# DAC_Board.net
KiCad netlist of a schematic drawn in Altium Designer
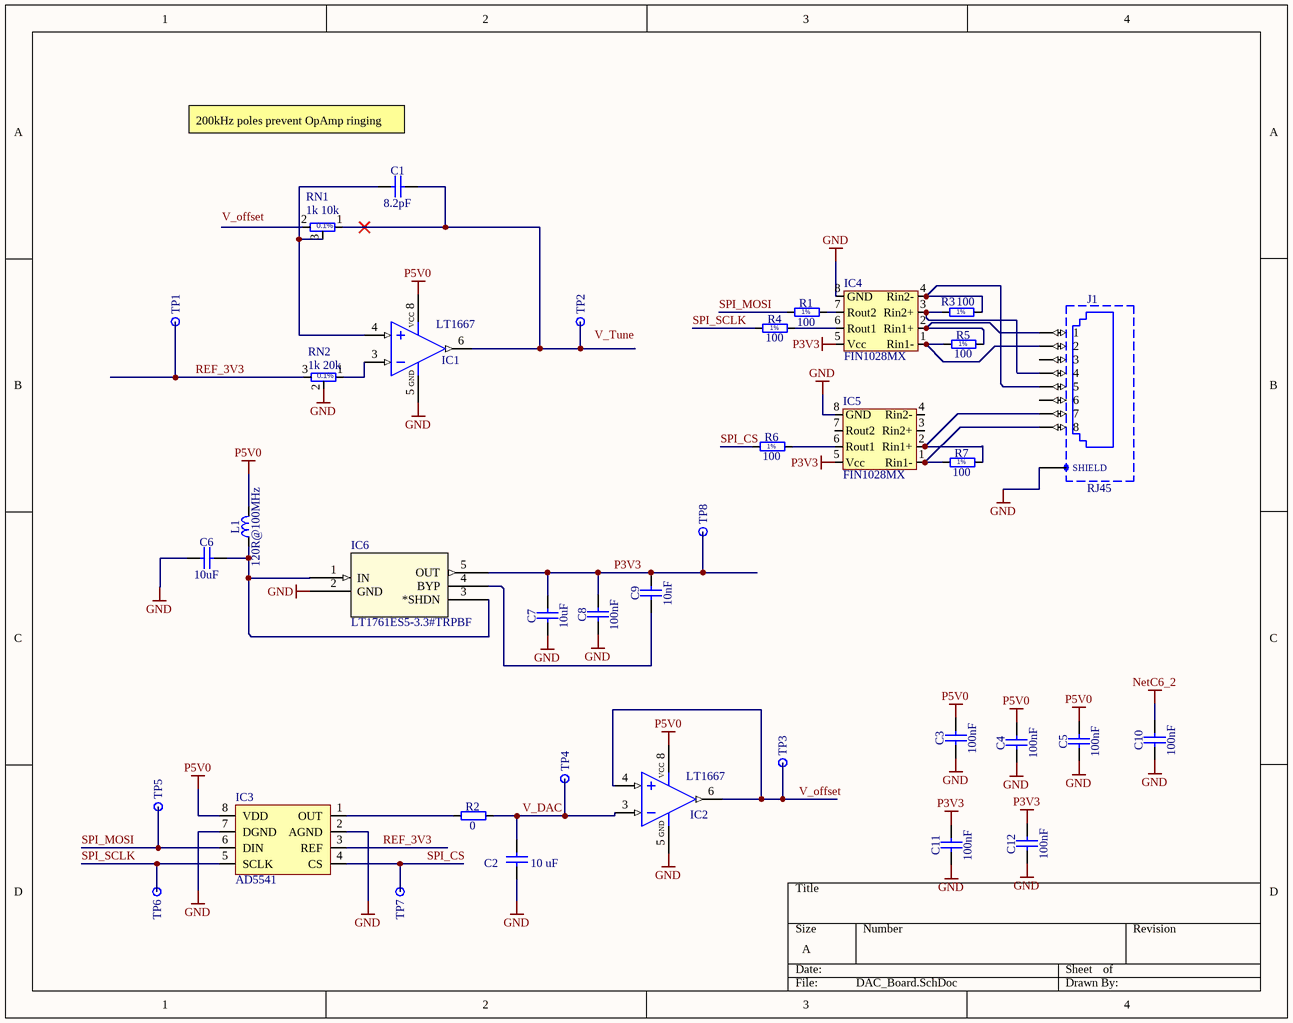
[diagram p0: DAC_Board.SchDoc]

(export (version "E")
  (design (tool "Eeschema 10.0.6"))
  (components
    (comp (ref "C1")
      (value "8.2pF")
      (footprint "CAPC1608X87N")
      (description "Non-polarised capacitor")
      (fields
        (field (name "PART NUMBER") "CC0603_8.2PF_50V_0.5PF_NP0")
        (field (name "VOLTAGE") "50V")
        (field (name "AUTHOR") "CERN DEM JLC")
      )
      (libsource (lib "Capacitors") (part "Capacitor - non polarized"))
    )
    (comp (ref "C2")
      (value "10 uF")
      (footprint "Capacitors SMD:CAPC5750X279N")
      (libsource (lib "Addons") (part "CAPF2220_10uF_35V_20%"))
    )
    (comp (ref "C3")
      (value "100nF")
      (footprint "CAPC1608X87N")
      (description "Non-polarised capacitor")
      (fields
        (field (name "PART NUMBER") "CC0603_100NF_50V_10%_X7R")
        (field (name "VOLTAGE") "50V")
        (field (name "AUTHOR") "CERN DEM JLC")
      )
      (libsource (lib "Capacitors") (part "Capacitor - non polarized"))
    )
    (comp (ref "C4")
      (value "100nF")
      (footprint "CAPC1608X87N")
      (description "Non-polarised capacitor")
      (fields
        (field (name "PART NUMBER") "CC0603_100NF_50V_10%_X7R")
        (field (name "VOLTAGE") "50V")
        (field (name "AUTHOR") "CERN DEM JLC")
      )
      (libsource (lib "Capacitors") (part "Capacitor - non polarized"))
    )
    (comp (ref "C5")
      (value "100nF")
      (footprint "CAPC1608X87N")
      (description "Non-polarised capacitor")
      (fields
        (field (name "PART NUMBER") "CC0603_100NF_50V_10%_X7R")
        (field (name "VOLTAGE") "50V")
        (field (name "AUTHOR") "CERN DEM JLC")
      )
      (libsource (lib "Capacitors") (part "Capacitor - non polarized"))
    )
    (comp (ref "C6")
      (value "10uF")
      (footprint "CAPC3216X180N")
      (description "Non-polarised capacitor")
      (fields
        (field (name "PART NUMBER") "CC1206_10UF_25V_10%_X7R")
        (field (name "VOLTAGE") "25V")
        (field (name "AUTHOR") "CERN DEM JLC")
      )
      (libsource (lib "Capacitors") (part "Capacitor - non polarized"))
    )
    (comp (ref "C7")
      (value "10uF")
      (footprint "CAPC3216X180N")
      (description "Non-polarised capacitor")
      (fields
        (field (name "PART NUMBER") "CC1206_10UF_25V_10%_X7R")
        (field (name "VOLTAGE") "25V")
        (field (name "AUTHOR") "CERN DEM JLC")
      )
      (libsource (lib "Capacitors") (part "Capacitor - non polarized"))
    )
    (comp (ref "C8")
      (value "100nF")
      (footprint "CAPC1608X87N")
      (description "Non-polarised capacitor")
      (fields
        (field (name "PART NUMBER") "CC0603_100NF_50V_10%_X7R")
        (field (name "VOLTAGE") "50V")
        (field (name "AUTHOR") "CERN DEM JLC")
      )
      (libsource (lib "Capacitors") (part "Capacitor - non polarized"))
    )
    (comp (ref "C9")
      (value "10nF")
      (footprint "CAPC1608X87N")
      (description "Non-polarised capacitor")
      (fields
        (field (name "PART NUMBER") "CC0603_10NF_50V_10%_X7R")
        (field (name "VOLTAGE") "50V")
        (field (name "AUTHOR") "CERN DEM JLC")
      )
      (libsource (lib "Capacitors") (part "Capacitor - non polarized"))
    )
    (comp (ref "C10")
      (value "100nF")
      (footprint "CAPC1608X87N")
      (description "Non-polarised capacitor")
      (fields
        (field (name "PART NUMBER") "CC0603_100NF_50V_10%_X7R")
        (field (name "VOLTAGE") "50V")
        (field (name "AUTHOR") "CERN DEM JLC")
      )
      (libsource (lib "Capacitors") (part "Capacitor - non polarized"))
    )
    (comp (ref "C11")
      (value "100nF")
      (footprint "CAPC1608X87N")
      (description "Non-polarised capacitor")
      (fields
        (field (name "PART NUMBER") "CC0603_100NF_50V_10%_X7R")
        (field (name "VOLTAGE") "50V")
        (field (name "AUTHOR") "CERN DEM JLC")
      )
      (libsource (lib "Capacitors") (part "Capacitor - non polarized"))
    )
    (comp (ref "C12")
      (value "100nF")
      (footprint "CAPC1608X87N")
      (description "Non-polarised capacitor")
      (fields
        (field (name "PART NUMBER") "CC0603_100NF_50V_10%_X7R")
        (field (name "VOLTAGE") "50V")
        (field (name "AUTHOR") "CERN DEM JLC")
      )
      (libsource (lib "Capacitors") (part "Capacitor - non polarized"))
    )
    (comp (ref "IC1")
      (value "LT1667")
      (footprint "SOIC127P600X175-8N")
      (description "0-5 V Rail to Rail op amp")
      (libsource (lib "LIBRARY_SCH") (part "LT1667"))
    )
    (comp (ref "IC2")
      (value "LT1667")
      (footprint "SOIC127P600X175-8N")
      (description "0-5 V Rail to Rail op amp")
      (libsource (lib "LIBRARY_SCH") (part "LT1667"))
    )
    (comp (ref "IC3")
      (value "AD5541")
      (footprint "AD5541")
      (description "16 bit serial DAC")
      (libsource (lib "LIBRARY_SCH") (part "AD5541"))
    )
    (comp (ref "IC4")
      (value "FIN1028MX")
      (footprint "FIN1028MX")
      (description "LVDS to TTL")
      (libsource (lib "LIBRARY_SCH") (part "FIN1028MX"))
    )
    (comp (ref "IC5")
      (value "FIN1028MX")
      (footprint "FIN1028MX")
      (description "LVDS to TTL")
      (libsource (lib "LIBRARY_SCH") (part "FIN1028MX"))
    )
    (comp (ref "IC6")
      (value "LT1761ES5-3.3#TRPBF")
      (footprint "LDO")
      (description "3.3 V LDO")
      (libsource (lib "LIBRARY_SCH") (part "LT1761ES5-3.3#TRPBF"))
    )
    (comp (ref "J1")
      (value "RJ45")
      (footprint "TYCO_6368150-1")
      (description "Connector RJ45 + Shield")
      (fields
        (field (name "PART NUMBER") "TYCO_6368150-1")
        (field (name "MANUFACTURER") "TYCO ELECTRONICS")
        (field (name "AUTHOR") "CERN DEM MR")
      )
      (libsource (lib "Connectors") (part "Connector RJ45 + Shield"))
    )
    (comp (ref "L1")
      (value "120R@100MHz")
      (footprint "INDC1608X95N")
      (description "Inductor")
      (fields
        (field (name "PART NUMBER") "IND0603_MURATA_BLM18PG121SN1D")
        (field (name "POWER") "2A")
        (field (name "AUTHOR") "CERN DEM BC")
      )
      (libsource (lib "Inductors & Transformers") (part "Inductor"))
    )
    (comp (ref "R1")
      (value "100")
      (footprint "RESC1608X55N")
      (description "Resistor - 1%")
      (fields
        (field (name "PART NUMBER") "R0603_100R_1%_0.1W_100PPM")
        (field (name "POWER") "0.1W")
        (field (name "AUTHOR") "CERN DEM JLC")
      )
      (libsource (lib "Resistors") (part "Resistor - 1%"))
    )
    (comp (ref "R2")
      (value "0")
      (footprint "RESC1608X55N")
      (description "Resistor")
      (fields
        (field (name "PART NUMBER") "R0603_0R_JUMPER")
        (field (name "MANUFACTURER") "GENERIC")
        (field (name "AUTHOR") "CERN DEM JLC")
      )
      (libsource (lib "Resistors") (part "Resistor"))
    )
    (comp (ref "R3")
      (value "100")
      (footprint "RESC1608X55N")
      (description "Resistor - 1%")
      (fields
        (field (name "PART NUMBER") "R0603_100R_1%_0.1W_100PPM")
        (field (name "POWER") "0.1W")
        (field (name "AUTHOR") "CERN DEM JLC")
      )
      (libsource (lib "Resistors") (part "Resistor - 1%"))
    )
    (comp (ref "R4")
      (value "100")
      (footprint "RESC1608X55N")
      (description "Resistor - 1%")
      (fields
        (field (name "PART NUMBER") "R0603_100R_1%_0.1W_100PPM")
        (field (name "POWER") "0.1W")
        (field (name "AUTHOR") "CERN DEM JLC")
      )
      (libsource (lib "Resistors") (part "Resistor - 1%"))
    )
    (comp (ref "R5")
      (value "100")
      (footprint "RESC1608X55N")
      (description "Resistor - 1%")
      (fields
        (field (name "PART NUMBER") "R0603_100R_1%_0.1W_100PPM")
        (field (name "POWER") "0.1W")
        (field (name "AUTHOR") "CERN DEM JLC")
      )
      (libsource (lib "Resistors") (part "Resistor - 1%"))
    )
    (comp (ref "R6")
      (value "100")
      (footprint "RESC1608X55N")
      (description "Resistor - 1%")
      (fields
        (field (name "PART NUMBER") "R0603_100R_1%_0.1W_100PPM")
        (field (name "POWER") "0.1W")
        (field (name "AUTHOR") "CERN DEM JLC")
      )
      (libsource (lib "Resistors") (part "Resistor - 1%"))
    )
    (comp (ref "R7")
      (value "100")
      (footprint "RESC1608X55N")
      (description "Resistor - 1%")
      (fields
        (field (name "PART NUMBER") "R0603_100R_1%_0.1W_100PPM")
        (field (name "POWER") "0.1W")
        (field (name "AUTHOR") "CERN DEM JLC")
      )
      (libsource (lib "Resistors") (part "Resistor - 1%"))
    )
    (comp (ref "RN1")
      (value "~")
      (footprint "SOT95P230X112-3N")
      (description "Resistor Network Divider - 0.1%")
      (libsource (lib "LIBRARY_SCH") (part "RN_1k_10k_VISHAY_MPMT10011002AT1"))
    )
    (comp (ref "RN2")
      (value "~")
      (footprint "SOT95P230X112-3N")
      (description "Resistor Network Divider - 0.1%")
      (libsource (lib "LIBRARY_SCH") (part "RN_1k_20k_VISHAY_MPMT10012002AT1"))
    )
    (comp (ref "TP1")
      (value "Test Point")
      (footprint "TPS127")
      (fields (field (name "PART NUMBER") "SMD_PAD_1.27X1.27MM") (field (name "AUTHOR") "CERN DEM JLC"))
      (libsource (lib "Eletro-mechanical") (part "Test Point"))
    )
    (comp (ref "TP2")
      (value "Test Point")
      (footprint "TPS127")
      (fields (field (name "PART NUMBER") "SMD_PAD_1.27X1.27MM") (field (name "AUTHOR") "CERN DEM JLC"))
      (libsource (lib "Eletro-mechanical") (part "Test Point"))
    )
    (comp (ref "TP3")
      (value "Test Point")
      (footprint "TPS127")
      (fields (field (name "PART NUMBER") "SMD_PAD_1.27X1.27MM") (field (name "AUTHOR") "CERN DEM JLC"))
      (libsource (lib "Eletro-mechanical") (part "Test Point"))
    )
    (comp (ref "TP4")
      (value "Test Point")
      (footprint "TPS127")
      (fields (field (name "PART NUMBER") "SMD_PAD_1.27X1.27MM") (field (name "AUTHOR") "CERN DEM JLC"))
      (libsource (lib "Eletro-mechanical") (part "Test Point"))
    )
    (comp (ref "TP5")
      (value "Test Point")
      (footprint "TPS127")
      (fields (field (name "PART NUMBER") "SMD_PAD_1.27X1.27MM") (field (name "AUTHOR") "CERN DEM JLC"))
      (libsource (lib "Eletro-mechanical") (part "Test Point"))
    )
    (comp (ref "TP6")
      (value "Test Point")
      (footprint "TPS127")
      (fields (field (name "PART NUMBER") "SMD_PAD_1.27X1.27MM") (field (name "AUTHOR") "CERN DEM JLC"))
      (libsource (lib "Eletro-mechanical") (part "Test Point"))
    )
    (comp (ref "TP7")
      (value "Test Point")
      (footprint "TPS127")
      (fields (field (name "PART NUMBER") "SMD_PAD_1.27X1.27MM") (field (name "AUTHOR") "CERN DEM JLC"))
      (libsource (lib "Eletro-mechanical") (part "Test Point"))
    )
    (comp (ref "TP8")
      (value "Test Point")
      (footprint "TPS127")
      (fields (field (name "PART NUMBER") "SMD_PAD_1.27X1.27MM") (field (name "AUTHOR") "CERN DEM JLC"))
      (libsource (lib "Eletro-mechanical") (part "Test Point"))
    )
  )
  (nets
    (net (code "1") (name "/REF_3V3") (class "Default")
      (node (ref "IC3") (pin "3") (pinfunction "REF_3") (pintype "passive"))
      (node (ref "RN2") (pin "3") (pinfunction "2_3") (pintype "passive"))
      (node (ref "TP1") (pin "1") (pinfunction "1_1") (pintype "bidirectional"))
    )
    (net (code "2") (name "/SPI_CS") (class "Default")
      (node (ref "IC3") (pin "4") (pinfunction "CS_4") (pintype "passive"))
      (node (ref "R6") (pin "1") (pinfunction "1_1") (pintype "passive"))
      (node (ref "TP7") (pin "1") (pinfunction "1_1") (pintype "bidirectional"))
    )
    (net (code "3") (name "/SPI_MOSI") (class "Default")
      (node (ref "IC3") (pin "6") (pinfunction "DIN_6") (pintype "passive"))
      (node (ref "R1") (pin "1") (pinfunction "1_1") (pintype "passive"))
      (node (ref "TP5") (pin "1") (pinfunction "1_1") (pintype "bidirectional"))
    )
    (net (code "4") (name "/SPI_SCLK") (class "Default")
      (node (ref "IC3") (pin "5") (pinfunction "SCLK_5") (pintype "passive"))
      (node (ref "R4") (pin "1") (pinfunction "1_1") (pintype "passive"))
      (node (ref "TP6") (pin "1") (pinfunction "1_1") (pintype "bidirectional"))
    )
    (net (code "5") (name "/V_DAC") (class "Default")
      (node (ref "C2") (pin "2") (pinfunction "2_2") (pintype "passive"))
      (node (ref "IC2") (pin "3") (pinfunction "IN-_3") (pintype "input"))
      (node (ref "R2") (pin "2") (pinfunction "2_2") (pintype "passive"))
      (node (ref "TP4") (pin "1") (pinfunction "1_1") (pintype "bidirectional"))
    )
    (net (code "7") (name "/V_offset") (class "Default")
      (node (ref "IC2") (pin "4") (pinfunction "IN+_4") (pintype "input"))
      (node (ref "IC2") (pin "6") (pinfunction "OUT_6") (pintype "output"))
      (node (ref "TP3") (pin "1") (pinfunction "1_1") (pintype "bidirectional"))
    )
    (net (code "8") (name "GND") (class "Default")
      (node (ref "C10") (pin "1") (pinfunction "1_1") (pintype "passive"))
      (node (ref "C11") (pin "1") (pinfunction "1_1") (pintype "passive"))
      (node (ref "C12") (pin "1") (pinfunction "1_1") (pintype "passive"))
      (node (ref "C2") (pin "1") (pinfunction "1_1") (pintype "passive"))
      (node (ref "C3") (pin "1") (pinfunction "1_1") (pintype "passive"))
      (node (ref "C4") (pin "1") (pinfunction "1_1") (pintype "passive"))
      (node (ref "C5") (pin "1") (pinfunction "1_1") (pintype "passive"))
      (node (ref "C6") (pin "1") (pinfunction "1_1") (pintype "passive"))
      (node (ref "C7") (pin "1") (pinfunction "1_1") (pintype "passive"))
      (node (ref "C8") (pin "1") (pinfunction "1_1") (pintype "passive"))
      (node (ref "IC1") (pin "5") (pinfunction "GND_5") (pintype "power_in"))
      (node (ref "IC2") (pin "5") (pinfunction "GND_5") (pintype "power_in"))
      (node (ref "IC3") (pin "2") (pinfunction "AGND_2") (pintype "passive"))
      (node (ref "IC3") (pin "7") (pinfunction "DGND_7") (pintype "passive"))
      (node (ref "IC4") (pin "8") (pinfunction "GND_8") (pintype "passive"))
      (node (ref "IC5") (pin "8") (pinfunction "GND_8") (pintype "passive"))
      (node (ref "IC6") (pin "2") (pinfunction "GND_2") (pintype "power_in"))
      (node (ref "J1") (pin "SHIELD") (pinfunction "SHIELD_SHIELD") (pintype "passive"))
      (node (ref "RN2") (pin "2") (pinfunction "2_2") (pintype "passive"))
    )
    (net (code "9") (name "Net-(IC1-IN+)") (class "Default")
      (node (ref "C1") (pin "1") (pinfunction "1_1") (pintype "passive"))
      (node (ref "IC1") (pin "4") (pinfunction "IN+_4") (pintype "input"))
      (node (ref "RN1") (pin "3") (pinfunction "3_3") (pintype "passive"))
    )
    (net (code "10") (name "Net-(IC1-IN-)") (class "Default")
      (node (ref "IC1") (pin "3") (pinfunction "IN-_3") (pintype "input"))
      (node (ref "RN2") (pin "1") (pinfunction "1_1") (pintype "passive"))
    )
    (net (code "11") (name "Net-(IC1-OUT)") (class "Default")
      (node (ref "C1") (pin "2") (pinfunction "2_2") (pintype "passive"))
      (node (ref "IC1") (pin "6") (pinfunction "OUT_6") (pintype "output"))
      (node (ref "RN1") (pin "1") (pinfunction "1_1") (pintype "passive"))
      (node (ref "TP2") (pin "1") (pinfunction "1_1") (pintype "bidirectional"))
    )
    (net (code "12") (name "Net-(IC3-OUT)") (class "Default")
      (node (ref "IC3") (pin "1") (pinfunction "OUT_1") (pintype "passive"))
      (node (ref "R2") (pin "1") (pinfunction "1_1") (pintype "passive"))
    )
    (net (code "13") (name "Net-(IC4-Rin1+)") (class "Default")
      (node (ref "IC4") (pin "2") (pinfunction "Rin1+_2") (pintype "passive"))
      (node (ref "J1") (pin "1") (pinfunction "1_1") (pintype "bidirectional"))
      (node (ref "R5") (pin "2") (pinfunction "2_2") (pintype "passive"))
    )
    (net (code "14") (name "Net-(IC4-Rin1-)") (class "Default")
      (node (ref "IC4") (pin "1") (pinfunction "Rin1-_1") (pintype "passive"))
      (node (ref "J1") (pin "2") (pinfunction "2_2") (pintype "bidirectional"))
      (node (ref "R5") (pin "1") (pinfunction "1_1") (pintype "passive"))
    )
    (net (code "15") (name "Net-(IC4-Rin2+)") (class "Default")
      (node (ref "IC4") (pin "3") (pinfunction "Rin2+_3") (pintype "passive"))
      (node (ref "J1") (pin "4") (pinfunction "4_4") (pintype "bidirectional"))
      (node (ref "R3") (pin "1") (pinfunction "1_1") (pintype "passive"))
    )
    (net (code "16") (name "Net-(IC4-Rin2-)") (class "Default")
      (node (ref "IC4") (pin "4") (pinfunction "Rin2-_4") (pintype "passive"))
      (node (ref "J1") (pin "5") (pinfunction "5_5") (pintype "bidirectional"))
      (node (ref "R3") (pin "2") (pinfunction "2_2") (pintype "passive"))
    )
    (net (code "17") (name "Net-(IC4-Rout1)") (class "Default")
      (node (ref "IC4") (pin "6") (pinfunction "Rout1_6") (pintype "passive"))
      (node (ref "R4") (pin "2") (pinfunction "2_2") (pintype "passive"))
    )
    (net (code "18") (name "Net-(IC4-Rout2)") (class "Default")
      (node (ref "IC4") (pin "7") (pinfunction "Rout2_7") (pintype "passive"))
      (node (ref "R1") (pin "2") (pinfunction "2_2") (pintype "passive"))
    )
    (net (code "19") (name "Net-(IC5-Rin1+)") (class "Default")
      (node (ref "IC5") (pin "2") (pinfunction "Rin1+_2") (pintype "passive"))
      (node (ref "J1") (pin "7") (pinfunction "7_7") (pintype "bidirectional"))
      (node (ref "R7") (pin "2") (pinfunction "2_2") (pintype "passive"))
    )
    (net (code "20") (name "Net-(IC5-Rin1-)") (class "Default")
      (node (ref "IC5") (pin "1") (pinfunction "Rin1-_1") (pintype "passive"))
      (node (ref "J1") (pin "8") (pinfunction "8_8") (pintype "bidirectional"))
      (node (ref "R7") (pin "1") (pinfunction "1_1") (pintype "passive"))
    )
    (net (code "21") (name "Net-(IC5-Rout1)") (class "Default")
      (node (ref "IC5") (pin "6") (pinfunction "Rout1_6") (pintype "passive"))
      (node (ref "R6") (pin "2") (pinfunction "2_2") (pintype "passive"))
    )
    (net (code "22") (name "Net-(IC6-*SHDN)") (class "Default")
      (node (ref "C6") (pin "2") (pinfunction "2_2") (pintype "passive"))
      (node (ref "IC6") (pin "1") (pinfunction "IN_1") (pintype "input"))
      (node (ref "IC6") (pin "3") (pinfunction "*SHDN_3") (pintype "passive"))
      (node (ref "L1") (pin "1") (pinfunction "1_1") (pintype "passive"))
    )
    (net (code "23") (name "Net-(IC6-BYP)") (class "Default")
      (node (ref "C9") (pin "1") (pinfunction "1_1") (pintype "passive"))
      (node (ref "IC6") (pin "4") (pinfunction "BYP_4") (pintype "passive"))
    )
    (net (code "24") (name "NetC6_2") (class "Default")
      (node (ref "C10") (pin "2") (pinfunction "2_2") (pintype "passive"))
    )
    (net (code "25") (name "P3V3") (class "Default")
      (node (ref "C11") (pin "2") (pinfunction "2_2") (pintype "passive"))
      (node (ref "C12") (pin "2") (pinfunction "2_2") (pintype "passive"))
      (node (ref "C7") (pin "2") (pinfunction "2_2") (pintype "passive"))
      (node (ref "C8") (pin "2") (pinfunction "2_2") (pintype "passive"))
      (node (ref "C9") (pin "2") (pinfunction "2_2") (pintype "passive"))
      (node (ref "IC4") (pin "5") (pinfunction "Vcc_5") (pintype "passive"))
      (node (ref "IC5") (pin "5") (pinfunction "Vcc_5") (pintype "passive"))
      (node (ref "IC6") (pin "5") (pinfunction "OUT_5") (pintype "output"))
      (node (ref "TP8") (pin "1") (pinfunction "1_1") (pintype "bidirectional"))
    )
    (net (code "26") (name "P5V0") (class "Default")
      (node (ref "C3") (pin "2") (pinfunction "2_2") (pintype "passive"))
      (node (ref "C4") (pin "2") (pinfunction "2_2") (pintype "passive"))
      (node (ref "C5") (pin "2") (pinfunction "2_2") (pintype "passive"))
      (node (ref "IC1") (pin "8") (pinfunction "V+_8") (pintype "power_in"))
      (node (ref "IC2") (pin "8") (pinfunction "V+_8") (pintype "power_in"))
      (node (ref "IC3") (pin "8") (pinfunction "VDD_8") (pintype "passive"))
      (node (ref "L1") (pin "2") (pinfunction "2_2") (pintype "passive"))
    )
    (net (code "27") (name "unconnected-(IC5-Rin2+-Pad3)") (class "Default")
      (node (ref "IC5") (pin "3") (pinfunction "Rin2+_3") (pintype "passive"))
    )
    (net (code "28") (name "unconnected-(IC5-Rin2--Pad4)") (class "Default")
      (node (ref "IC5") (pin "4") (pinfunction "Rin2-_4") (pintype "passive"))
    )
    (net (code "29") (name "unconnected-(IC5-Rout2-Pad7)") (class "Default")
      (node (ref "IC5") (pin "7") (pinfunction "Rout2_7") (pintype "passive"))
    )
    (net (code "30") (name "unconnected-(J1-Pad3)") (class "Default")
      (node (ref "J1") (pin "3") (pinfunction "3_3") (pintype "bidirectional"))
    )
    (net (code "31") (name "unconnected-(J1-Pad6)") (class "Default")
      (node (ref "J1") (pin "6") (pinfunction "6_6") (pintype "bidirectional"))
    )
    (net (code "32") (name "unconnected-(RN1-Pad2)") (class "Default")
      (node (ref "RN1") (pin "2") (pinfunction "2_2") (pintype "passive"))
    )
  )
)
